# DCF-Interface-1.net
KiCad netlist of a schematic drawn in Altium Designer
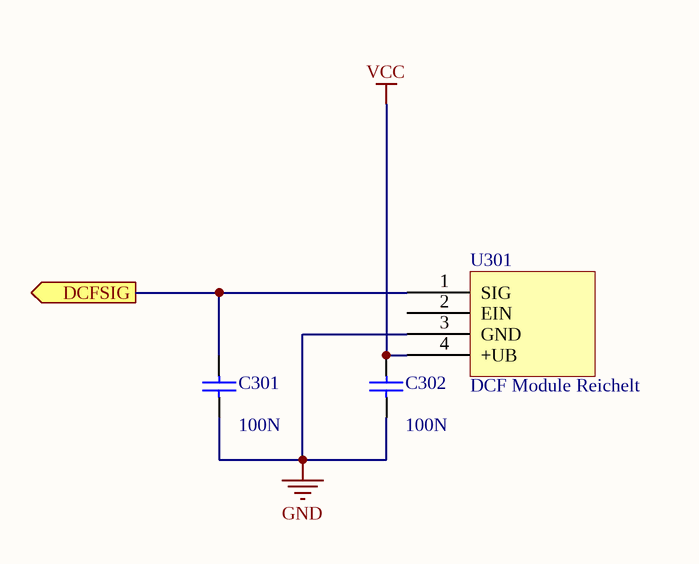
[diagram p0: DCF-Interface-1.SchDoc]

(export (version "E")
  (design (tool "Eeschema 10.0.6"))
  (components
    (comp (ref "C301")
      (value "100N")
      (footprint "RCL 0805")
      (description "Capacitor")
      (fields (field (name "Comment") "Cap") (field (name "PUBLISHER") "Altium Limited"))
      (libsource (lib "Miscellaneous Devices") (part "Cap"))
    )
    (comp (ref "C302")
      (value "100N")
      (footprint "RCL 0805")
      (description "Capacitor")
      (fields (field (name "Comment") "Cap") (field (name "PUBLISHER") "Altium Limited"))
      (libsource (lib "Miscellaneous Devices") (part "Cap"))
    )
    (comp (ref "U301")
      (value "DCF Module Reichelt")
      (footprint "DCF MODUL REICHELT")
      (libsource (lib "MyLibrary") (part "DCF Module Reichelt"))
    )
  )
  (nets
    (net (code "1") (name "/DCFSIG") (class "Default")
      (node (ref "C301") (pin "2") (pinfunction "2_2") (pintype "passive"))
      (node (ref "U301") (pin "1") (pinfunction "SIG_1") (pintype "passive"))
    )
    (net (code "2") (name "GND") (class "Default")
      (node (ref "C301") (pin "1") (pinfunction "1_1") (pintype "passive"))
      (node (ref "C302") (pin "1") (pinfunction "1_1") (pintype "passive"))
      (node (ref "U301") (pin "3") (pinfunction "GND_3") (pintype "passive"))
    )
    (net (code "3") (name "VCC") (class "Default")
      (node (ref "C302") (pin "2") (pinfunction "2_2") (pintype "passive"))
      (node (ref "U301") (pin "4") (pinfunction "+UB_4") (pintype "passive"))
    )
    (net (code "4") (name "unconnected-(U301-EIN-Pad2)") (class "Default")
      (node (ref "U301") (pin "2") (pinfunction "EIN_2") (pintype "passive"))
    )
  )
)
